# RPiXBee.net
KiCad netlist of a schematic drawn in EAGLE
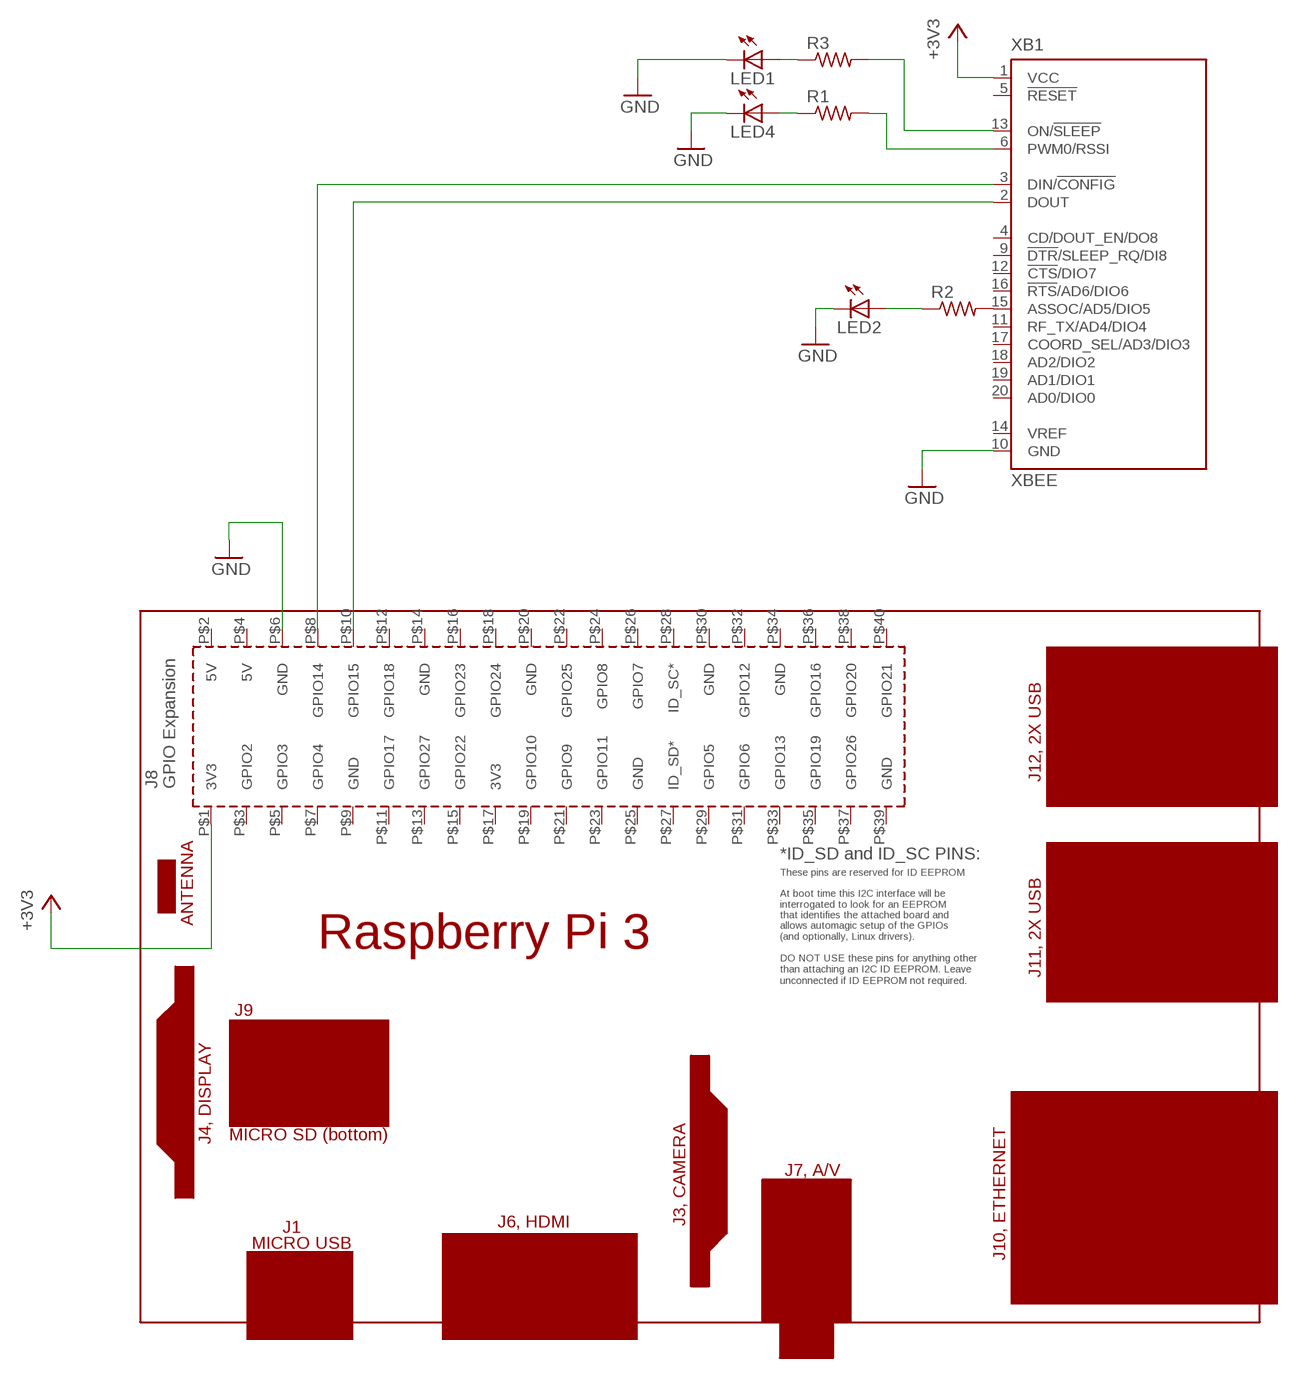
[diagram p0: schematic, sheet 1]

(export (version "E")
  (design (tool "Eeschema 10.0.6"))
  (components
    (comp (ref "LED1")
      (value "LEDCHIP-LED0603")
      (footprint "eagle-import:CHIP-LED0603")
      (libsource (lib "eagle-import") (part "LEDCHIP-LED0603"))
    )
    (comp (ref "LED2")
      (value "LEDCHIP-LED0603")
      (footprint "eagle-import:CHIP-LED0603")
      (libsource (lib "eagle-import") (part "LEDCHIP-LED0603"))
    )
    (comp (ref "LED4")
      (value "LEDCHIP-LED0603")
      (footprint "eagle-import:CHIP-LED0603")
      (libsource (lib "eagle-import") (part "LEDCHIP-LED0603"))
    )
    (comp (ref "PCB1")
      (value "RPI3NO-CONNECTORS")
      (footprint "eagle-import:RPI3-NO-CONNECTORS")
      (libsource (lib "eagle-import") (part "RPI3NO-CONNECTORS"))
    )
    (comp (ref "R1")
      (value "R-US_R0603")
      (footprint "eagle-import:R0603")
      (libsource (lib "eagle-import") (part "R-US_R0603"))
    )
    (comp (ref "R2")
      (value "R-US_R0603")
      (footprint "eagle-import:R0603")
      (libsource (lib "eagle-import") (part "R-US_R0603"))
    )
    (comp (ref "R3")
      (value "R-US_R0603")
      (footprint "eagle-import:R0603")
      (libsource (lib "eagle-import") (part "R-US_R0603"))
    )
    (comp (ref "XB1")
      (value "XBEE")
      (footprint "eagle-import:XBEE")
      (fields (field (name "MPN") "XBP24-Z7UIT-004"))
      (libsource (lib "eagle-import") (part "XBEE"))
    )
  )
  (nets
    (net (code "1") (name "+3V3") (class "Default")
      (node (ref "PCB1") (pin "P$1") (pinfunction "3V3_P$1") (pintype "bidirectional"))
      (node (ref "XB1") (pin "1") (pinfunction "VCC_1") (pintype "power_in"))
    )
    (net (code "2") (name "GND") (class "Default")
      (node (ref "LED1") (pin "C") (pinfunction "C_C") (pintype "passive"))
      (node (ref "LED2") (pin "C") (pinfunction "C_C") (pintype "passive"))
      (node (ref "LED4") (pin "C") (pinfunction "C_C") (pintype "passive"))
      (node (ref "PCB1") (pin "P$6") (pinfunction "GND_P$6") (pintype "bidirectional"))
      (node (ref "XB1") (pin "10") (pinfunction "GND_10") (pintype "power_in"))
    )
    (net (code "3") (name "Net-(LED1-PadA)") (class "Default")
      (node (ref "LED1") (pin "A") (pinfunction "A_A") (pintype "passive"))
      (node (ref "R3") (pin "1") (pinfunction "1_1") (pintype "passive"))
    )
    (net (code "4") (name "Net-(LED2-PadA)") (class "Default")
      (node (ref "LED2") (pin "A") (pinfunction "A_A") (pintype "passive"))
      (node (ref "R2") (pin "1") (pinfunction "1_1") (pintype "passive"))
    )
    (net (code "5") (name "Net-(LED4-PadA)") (class "Default")
      (node (ref "LED4") (pin "A") (pinfunction "A_A") (pintype "passive"))
      (node (ref "R1") (pin "1") (pinfunction "1_1") (pintype "passive"))
    )
    (net (code "6") (name "Net-(PCB1-GPIO14)") (class "Default")
      (node (ref "PCB1") (pin "P$8") (pinfunction "GPIO14_P$8") (pintype "bidirectional"))
      (node (ref "XB1") (pin "3") (pinfunction "DIN/~{CONFIG}_3") (pintype "input"))
    )
    (net (code "7") (name "Net-(PCB1-GPIO15)") (class "Default")
      (node (ref "PCB1") (pin "P$10") (pinfunction "GPIO15_P$10") (pintype "bidirectional"))
      (node (ref "XB1") (pin "2") (pinfunction "DOUT_2") (pintype "output"))
    )
    (net (code "8") (name "Net-(XB1-ASSOC{slash}AD5{slash}DIO5)") (class "Default")
      (node (ref "R2") (pin "2") (pinfunction "2_2") (pintype "passive"))
      (node (ref "XB1") (pin "15") (pinfunction "ASSOC/AD5/DIO5_15") (pintype "bidirectional"))
    )
    (net (code "9") (name "Net-(XB1-ON{slash}~{SLEEP})") (class "Default")
      (node (ref "R3") (pin "2") (pinfunction "2_2") (pintype "passive"))
      (node (ref "XB1") (pin "13") (pinfunction "ON/~{SLEEP}_13") (pintype "output"))
    )
    (net (code "10") (name "Net-(XB1-PWM0{slash}RSSI)") (class "Default")
      (node (ref "R1") (pin "2") (pinfunction "2_2") (pintype "passive"))
      (node (ref "XB1") (pin "6") (pinfunction "PWM0/RSSI_6") (pintype "output"))
    )
    (net (code "11") (name "unconnected-(PCB1-3V3-PadP$17)") (class "Default")
      (node (ref "PCB1") (pin "P$17") (pinfunction "3V3_P$17") (pintype "bidirectional"))
    )
    (net (code "12") (name "unconnected-(PCB1-5V-PadP$2)") (class "Default")
      (node (ref "PCB1") (pin "P$2") (pinfunction "5V_P$2") (pintype "bidirectional"))
    )
    (net (code "13") (name "unconnected-(PCB1-5V-PadP$4)") (class "Default")
      (node (ref "PCB1") (pin "P$4") (pinfunction "5V_P$4") (pintype "bidirectional"))
    )
    (net (code "14") (name "unconnected-(PCB1-GND-PadP$9)") (class "Default")
      (node (ref "PCB1") (pin "P$9") (pinfunction "GND_P$9") (pintype "bidirectional"))
    )
    (net (code "15") (name "unconnected-(PCB1-GND-PadP$14)") (class "Default")
      (node (ref "PCB1") (pin "P$14") (pinfunction "GND_P$14") (pintype "bidirectional"))
    )
    (net (code "16") (name "unconnected-(PCB1-GND-PadP$20)") (class "Default")
      (node (ref "PCB1") (pin "P$20") (pinfunction "GND_P$20") (pintype "bidirectional"))
    )
    (net (code "17") (name "unconnected-(PCB1-GND-PadP$25)") (class "Default")
      (node (ref "PCB1") (pin "P$25") (pinfunction "GND_P$25") (pintype "bidirectional"))
    )
    (net (code "18") (name "unconnected-(PCB1-GND-PadP$30)") (class "Default")
      (node (ref "PCB1") (pin "P$30") (pinfunction "GND_P$30") (pintype "bidirectional"))
    )
    (net (code "19") (name "unconnected-(PCB1-GND-PadP$34)") (class "Default")
      (node (ref "PCB1") (pin "P$34") (pinfunction "GND_P$34") (pintype "bidirectional"))
    )
    (net (code "20") (name "unconnected-(PCB1-GND-PadP$39)") (class "Default")
      (node (ref "PCB1") (pin "P$39") (pinfunction "GND_P$39") (pintype "bidirectional"))
    )
    (net (code "21") (name "unconnected-(PCB1-GPIO2-PadP$3)") (class "Default")
      (node (ref "PCB1") (pin "P$3") (pinfunction "GPIO2_P$3") (pintype "bidirectional"))
    )
    (net (code "22") (name "unconnected-(PCB1-GPIO3-PadP$5)") (class "Default")
      (node (ref "PCB1") (pin "P$5") (pinfunction "GPIO3_P$5") (pintype "bidirectional"))
    )
    (net (code "23") (name "unconnected-(PCB1-GPIO4-PadP$7)") (class "Default")
      (node (ref "PCB1") (pin "P$7") (pinfunction "GPIO4_P$7") (pintype "bidirectional"))
    )
    (net (code "24") (name "unconnected-(PCB1-GPIO5-PadP$29)") (class "Default")
      (node (ref "PCB1") (pin "P$29") (pinfunction "GPIO5_P$29") (pintype "bidirectional"))
    )
    (net (code "25") (name "unconnected-(PCB1-GPIO6-PadP$31)") (class "Default")
      (node (ref "PCB1") (pin "P$31") (pinfunction "GPIO6_P$31") (pintype "bidirectional"))
    )
    (net (code "26") (name "unconnected-(PCB1-GPIO7-PadP$26)") (class "Default")
      (node (ref "PCB1") (pin "P$26") (pinfunction "GPIO7_P$26") (pintype "bidirectional"))
    )
    (net (code "27") (name "unconnected-(PCB1-GPIO8-PadP$24)") (class "Default")
      (node (ref "PCB1") (pin "P$24") (pinfunction "GPIO8_P$24") (pintype "bidirectional"))
    )
    (net (code "28") (name "unconnected-(PCB1-GPIO9-PadP$21)") (class "Default")
      (node (ref "PCB1") (pin "P$21") (pinfunction "GPIO9_P$21") (pintype "bidirectional"))
    )
    (net (code "29") (name "unconnected-(PCB1-GPIO10-PadP$19)") (class "Default")
      (node (ref "PCB1") (pin "P$19") (pinfunction "GPIO10_P$19") (pintype "bidirectional"))
    )
    (net (code "30") (name "unconnected-(PCB1-GPIO11-PadP$23)") (class "Default")
      (node (ref "PCB1") (pin "P$23") (pinfunction "GPIO11_P$23") (pintype "bidirectional"))
    )
    (net (code "31") (name "unconnected-(PCB1-GPIO12-PadP$32)") (class "Default")
      (node (ref "PCB1") (pin "P$32") (pinfunction "GPIO12_P$32") (pintype "bidirectional"))
    )
    (net (code "32") (name "unconnected-(PCB1-GPIO13-PadP$33)") (class "Default")
      (node (ref "PCB1") (pin "P$33") (pinfunction "GPIO13_P$33") (pintype "bidirectional"))
    )
    (net (code "33") (name "unconnected-(PCB1-GPIO16-PadP$36)") (class "Default")
      (node (ref "PCB1") (pin "P$36") (pinfunction "GPIO16_P$36") (pintype "bidirectional"))
    )
    (net (code "34") (name "unconnected-(PCB1-GPIO17-PadP$11)") (class "Default")
      (node (ref "PCB1") (pin "P$11") (pinfunction "GPIO17_P$11") (pintype "bidirectional"))
    )
    (net (code "35") (name "unconnected-(PCB1-GPIO18-PadP$12)") (class "Default")
      (node (ref "PCB1") (pin "P$12") (pinfunction "GPIO18_P$12") (pintype "bidirectional"))
    )
    (net (code "36") (name "unconnected-(PCB1-GPIO19-PadP$35)") (class "Default")
      (node (ref "PCB1") (pin "P$35") (pinfunction "GPIO19_P$35") (pintype "bidirectional"))
    )
    (net (code "37") (name "unconnected-(PCB1-GPIO20-PadP$38)") (class "Default")
      (node (ref "PCB1") (pin "P$38") (pinfunction "GPIO20_P$38") (pintype "bidirectional"))
    )
    (net (code "38") (name "unconnected-(PCB1-GPIO21-PadP$40)") (class "Default")
      (node (ref "PCB1") (pin "P$40") (pinfunction "GPIO21_P$40") (pintype "bidirectional"))
    )
    (net (code "39") (name "unconnected-(PCB1-GPIO22-PadP$15)") (class "Default")
      (node (ref "PCB1") (pin "P$15") (pinfunction "GPIO22_P$15") (pintype "bidirectional"))
    )
    (net (code "40") (name "unconnected-(PCB1-GPIO23-PadP$16)") (class "Default")
      (node (ref "PCB1") (pin "P$16") (pinfunction "GPIO23_P$16") (pintype "bidirectional"))
    )
    (net (code "41") (name "unconnected-(PCB1-GPIO24-PadP$18)") (class "Default")
      (node (ref "PCB1") (pin "P$18") (pinfunction "GPIO24_P$18") (pintype "bidirectional"))
    )
    (net (code "42") (name "unconnected-(PCB1-GPIO25-PadP$22)") (class "Default")
      (node (ref "PCB1") (pin "P$22") (pinfunction "GPIO25_P$22") (pintype "bidirectional"))
    )
    (net (code "43") (name "unconnected-(PCB1-GPIO26-PadP$37)") (class "Default")
      (node (ref "PCB1") (pin "P$37") (pinfunction "GPIO26_P$37") (pintype "bidirectional"))
    )
    (net (code "44") (name "unconnected-(PCB1-GPIO27-PadP$13)") (class "Default")
      (node (ref "PCB1") (pin "P$13") (pinfunction "GPIO27_P$13") (pintype "bidirectional"))
    )
    (net (code "45") (name "unconnected-(PCB1-ID_SC*-PadP$28)") (class "Default")
      (node (ref "PCB1") (pin "P$28") (pinfunction "ID_SC*_P$28") (pintype "bidirectional"))
    )
    (net (code "46") (name "unconnected-(PCB1-ID_SD*-PadP$27)") (class "Default")
      (node (ref "PCB1") (pin "P$27") (pinfunction "ID_SD*_P$27") (pintype "bidirectional"))
    )
    (net (code "47") (name "unconnected-(XB1-AD0{slash}DIO0-Pad20)") (class "Default")
      (node (ref "XB1") (pin "20") (pinfunction "AD0/DIO0_20") (pintype "bidirectional"))
    )
    (net (code "48") (name "unconnected-(XB1-AD1{slash}DIO1-Pad19)") (class "Default")
      (node (ref "XB1") (pin "19") (pinfunction "AD1/DIO1_19") (pintype "bidirectional"))
    )
    (net (code "49") (name "unconnected-(XB1-AD2{slash}DIO2-Pad18)") (class "Default")
      (node (ref "XB1") (pin "18") (pinfunction "AD2/DIO2_18") (pintype "bidirectional"))
    )
    (net (code "50") (name "unconnected-(XB1-CD{slash}DOUT_EN{slash}DO8-Pad4)") (class "Default")
      (node (ref "XB1") (pin "4") (pinfunction "CD/DOUT_EN/DO8_4") (pintype "output"))
    )
    (net (code "51") (name "unconnected-(XB1-COORD_SEL{slash}AD3{slash}DIO3-Pad17)") (class "Default")
      (node (ref "XB1") (pin "17") (pinfunction "COORD_SEL/AD3/DIO3_17") (pintype "bidirectional"))
    )
    (net (code "52") (name "unconnected-(XB1-RF_TX{slash}AD4{slash}DIO4-Pad11)") (class "Default")
      (node (ref "XB1") (pin "11") (pinfunction "RF_TX/AD4/DIO4_11") (pintype "bidirectional"))
    )
    (net (code "53") (name "unconnected-(XB1-VREF-Pad14)") (class "Default")
      (node (ref "XB1") (pin "14") (pinfunction "VREF_14") (pintype "input"))
    )
    (net (code "54") (name "unconnected-(XB1-~{CTS}{slash}DIO7-Pad12)") (class "Default")
      (node (ref "XB1") (pin "12") (pinfunction "~{CTS}/DIO7_12") (pintype "bidirectional"))
    )
    (net (code "55") (name "unconnected-(XB1-~{DTR}{slash}SLEEP_RQ{slash}DI8-Pad9)") (class "Default")
      (node (ref "XB1") (pin "9") (pinfunction "~{DTR}/SLEEP_RQ/DI8_9") (pintype "bidirectional"))
    )
    (net (code "56") (name "unconnected-(XB1-~{RESET}-Pad5)") (class "Default")
      (node (ref "XB1") (pin "5") (pinfunction "~{RESET}_5") (pintype "input"))
    )
    (net (code "57") (name "unconnected-(XB1-~{RTS}{slash}AD6{slash}DIO6-Pad16)") (class "Default")
      (node (ref "XB1") (pin "16") (pinfunction "~{RTS}/AD6/DIO6_16") (pintype "bidirectional"))
    )
  )
)
